# Wordclocktest.net
KiCad netlist of a schematic drawn in EAGLE
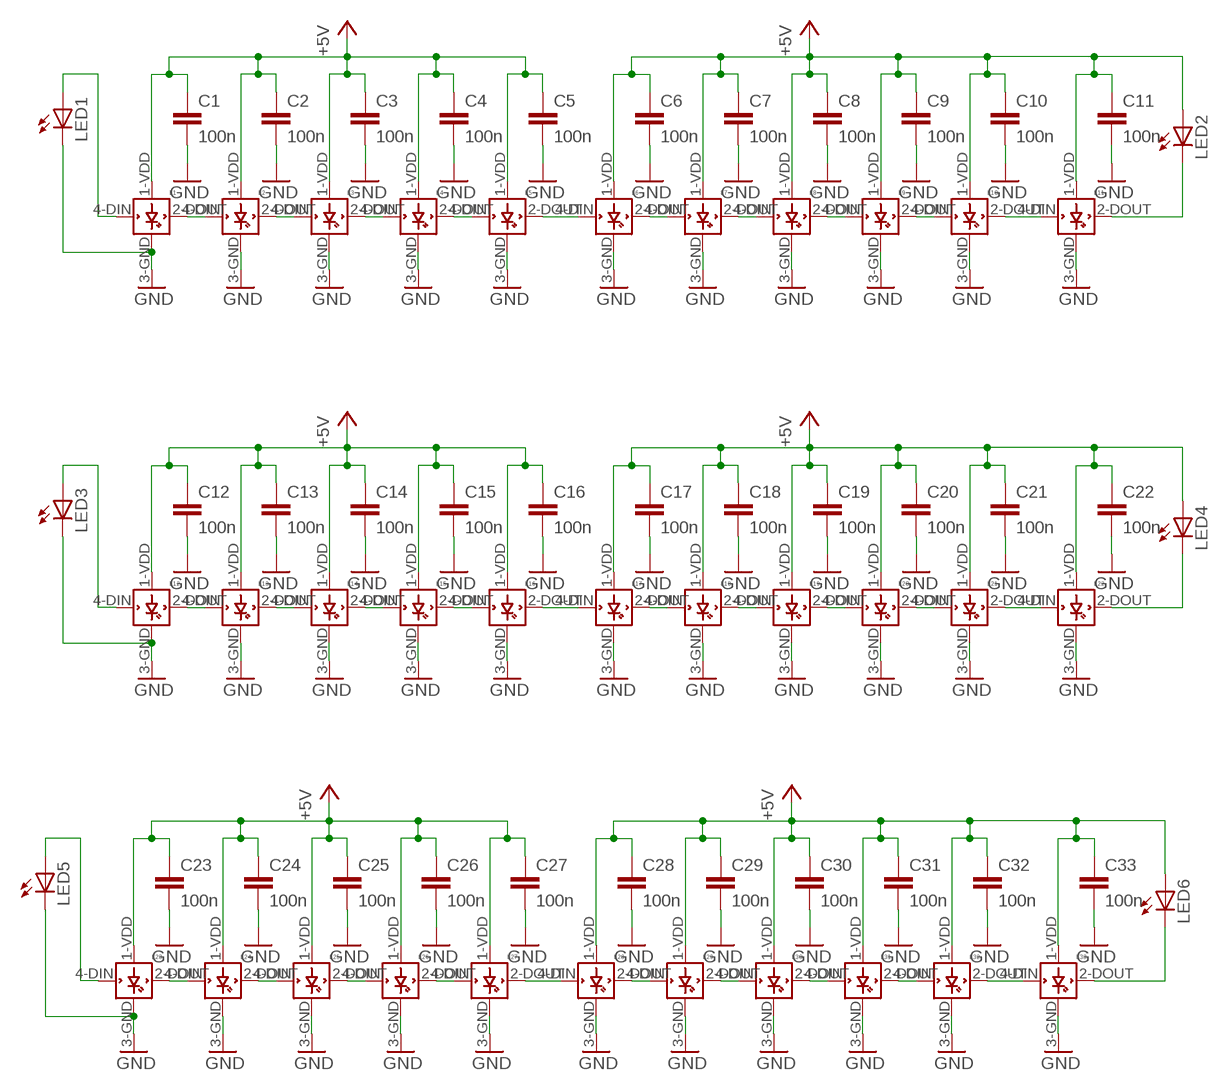
[diagram p0: schematic, sheet 1]

(export (version "E")
  (design (tool "Eeschema 10.0.6"))
  (components
    (comp (ref "C1")
      (value "100n")
      (footprint "eagle-import:C1310")
      (libsource (lib "eagle-import") (part "C-EUC1310"))
    )
    (comp (ref "C2")
      (value "100n")
      (footprint "eagle-import:C1310")
      (libsource (lib "eagle-import") (part "C-EUC1310"))
    )
    (comp (ref "C3")
      (value "100n")
      (footprint "eagle-import:C1310")
      (libsource (lib "eagle-import") (part "C-EUC1310"))
    )
    (comp (ref "C4")
      (value "100n")
      (footprint "eagle-import:C1310")
      (libsource (lib "eagle-import") (part "C-EUC1310"))
    )
    (comp (ref "C5")
      (value "100n")
      (footprint "eagle-import:C1310")
      (libsource (lib "eagle-import") (part "C-EUC1310"))
    )
    (comp (ref "C6")
      (value "100n")
      (footprint "eagle-import:C1310")
      (libsource (lib "eagle-import") (part "C-EUC1310"))
    )
    (comp (ref "C7")
      (value "100n")
      (footprint "eagle-import:C1310")
      (libsource (lib "eagle-import") (part "C-EUC1310"))
    )
    (comp (ref "C8")
      (value "100n")
      (footprint "eagle-import:C1310")
      (libsource (lib "eagle-import") (part "C-EUC1310"))
    )
    (comp (ref "C9")
      (value "100n")
      (footprint "eagle-import:C1310")
      (libsource (lib "eagle-import") (part "C-EUC1310"))
    )
    (comp (ref "C10")
      (value "100n")
      (footprint "eagle-import:C1310")
      (libsource (lib "eagle-import") (part "C-EUC1310"))
    )
    (comp (ref "C11")
      (value "100n")
      (footprint "eagle-import:C1310")
      (libsource (lib "eagle-import") (part "C-EUC1310"))
    )
    (comp (ref "C12")
      (value "100n")
      (footprint "eagle-import:C1310")
      (libsource (lib "eagle-import") (part "C-EUC1310"))
    )
    (comp (ref "C13")
      (value "100n")
      (footprint "eagle-import:C1310")
      (libsource (lib "eagle-import") (part "C-EUC1310"))
    )
    (comp (ref "C14")
      (value "100n")
      (footprint "eagle-import:C1310")
      (libsource (lib "eagle-import") (part "C-EUC1310"))
    )
    (comp (ref "C15")
      (value "100n")
      (footprint "eagle-import:C1310")
      (libsource (lib "eagle-import") (part "C-EUC1310"))
    )
    (comp (ref "C16")
      (value "100n")
      (footprint "eagle-import:C1310")
      (libsource (lib "eagle-import") (part "C-EUC1310"))
    )
    (comp (ref "C17")
      (value "100n")
      (footprint "eagle-import:C1310")
      (libsource (lib "eagle-import") (part "C-EUC1310"))
    )
    (comp (ref "C18")
      (value "100n")
      (footprint "eagle-import:C1310")
      (libsource (lib "eagle-import") (part "C-EUC1310"))
    )
    (comp (ref "C19")
      (value "100n")
      (footprint "eagle-import:C1310")
      (libsource (lib "eagle-import") (part "C-EUC1310"))
    )
    (comp (ref "C20")
      (value "100n")
      (footprint "eagle-import:C1310")
      (libsource (lib "eagle-import") (part "C-EUC1310"))
    )
    (comp (ref "C21")
      (value "100n")
      (footprint "eagle-import:C1310")
      (libsource (lib "eagle-import") (part "C-EUC1310"))
    )
    (comp (ref "C22")
      (value "100n")
      (footprint "eagle-import:C1310")
      (libsource (lib "eagle-import") (part "C-EUC1310"))
    )
    (comp (ref "C23")
      (value "100n")
      (footprint "eagle-import:C1310")
      (libsource (lib "eagle-import") (part "C-EUC1310"))
    )
    (comp (ref "C24")
      (value "100n")
      (footprint "eagle-import:C1310")
      (libsource (lib "eagle-import") (part "C-EUC1310"))
    )
    (comp (ref "C25")
      (value "100n")
      (footprint "eagle-import:C1310")
      (libsource (lib "eagle-import") (part "C-EUC1310"))
    )
    (comp (ref "C26")
      (value "100n")
      (footprint "eagle-import:C1310")
      (libsource (lib "eagle-import") (part "C-EUC1310"))
    )
    (comp (ref "C27")
      (value "100n")
      (footprint "eagle-import:C1310")
      (libsource (lib "eagle-import") (part "C-EUC1310"))
    )
    (comp (ref "C28")
      (value "100n")
      (footprint "eagle-import:C1310")
      (libsource (lib "eagle-import") (part "C-EUC1310"))
    )
    (comp (ref "C29")
      (value "100n")
      (footprint "eagle-import:C1310")
      (libsource (lib "eagle-import") (part "C-EUC1310"))
    )
    (comp (ref "C30")
      (value "100n")
      (footprint "eagle-import:C1310")
      (libsource (lib "eagle-import") (part "C-EUC1310"))
    )
    (comp (ref "C31")
      (value "100n")
      (footprint "eagle-import:C1310")
      (libsource (lib "eagle-import") (part "C-EUC1310"))
    )
    (comp (ref "C32")
      (value "100n")
      (footprint "eagle-import:C1310")
      (libsource (lib "eagle-import") (part "C-EUC1310"))
    )
    (comp (ref "C33")
      (value "100n")
      (footprint "eagle-import:C1310")
      (libsource (lib "eagle-import") (part "C-EUC1310"))
    )
    (comp (ref "L1")
      (value "WS2812B")
      (footprint "eagle-import:WS2812B")
      (libsource (lib "eagle-import") (part "WS2812B"))
    )
    (comp (ref "L2")
      (value "WS2812B")
      (footprint "eagle-import:WS2812B")
      (libsource (lib "eagle-import") (part "WS2812B"))
    )
    (comp (ref "L3")
      (value "WS2812B")
      (footprint "eagle-import:WS2812B")
      (libsource (lib "eagle-import") (part "WS2812B"))
    )
    (comp (ref "L4")
      (value "WS2812B")
      (footprint "eagle-import:WS2812B")
      (libsource (lib "eagle-import") (part "WS2812B"))
    )
    (comp (ref "L5")
      (value "WS2812B")
      (footprint "eagle-import:WS2812B")
      (libsource (lib "eagle-import") (part "WS2812B"))
    )
    (comp (ref "L6")
      (value "WS2812B")
      (footprint "eagle-import:WS2812B")
      (libsource (lib "eagle-import") (part "WS2812B"))
    )
    (comp (ref "L7")
      (value "WS2812B")
      (footprint "eagle-import:WS2812B")
      (libsource (lib "eagle-import") (part "WS2812B"))
    )
    (comp (ref "L8")
      (value "WS2812B")
      (footprint "eagle-import:WS2812B")
      (libsource (lib "eagle-import") (part "WS2812B"))
    )
    (comp (ref "L9")
      (value "WS2812B")
      (footprint "eagle-import:WS2812B")
      (libsource (lib "eagle-import") (part "WS2812B"))
    )
    (comp (ref "L10")
      (value "WS2812B")
      (footprint "eagle-import:WS2812B")
      (libsource (lib "eagle-import") (part "WS2812B"))
    )
    (comp (ref "L11")
      (value "WS2812B")
      (footprint "eagle-import:WS2812B")
      (libsource (lib "eagle-import") (part "WS2812B"))
    )
    (comp (ref "L12")
      (value "WS2812B")
      (footprint "eagle-import:WS2812B")
      (libsource (lib "eagle-import") (part "WS2812B"))
    )
    (comp (ref "L13")
      (value "WS2812B")
      (footprint "eagle-import:WS2812B")
      (libsource (lib "eagle-import") (part "WS2812B"))
    )
    (comp (ref "L14")
      (value "WS2812B")
      (footprint "eagle-import:WS2812B")
      (libsource (lib "eagle-import") (part "WS2812B"))
    )
    (comp (ref "L15")
      (value "WS2812B")
      (footprint "eagle-import:WS2812B")
      (libsource (lib "eagle-import") (part "WS2812B"))
    )
    (comp (ref "L16")
      (value "WS2812B")
      (footprint "eagle-import:WS2812B")
      (libsource (lib "eagle-import") (part "WS2812B"))
    )
    (comp (ref "L17")
      (value "WS2812B")
      (footprint "eagle-import:WS2812B")
      (libsource (lib "eagle-import") (part "WS2812B"))
    )
    (comp (ref "L18")
      (value "WS2812B")
      (footprint "eagle-import:WS2812B")
      (libsource (lib "eagle-import") (part "WS2812B"))
    )
    (comp (ref "L19")
      (value "WS2812B")
      (footprint "eagle-import:WS2812B")
      (libsource (lib "eagle-import") (part "WS2812B"))
    )
    (comp (ref "L20")
      (value "WS2812B")
      (footprint "eagle-import:WS2812B")
      (libsource (lib "eagle-import") (part "WS2812B"))
    )
    (comp (ref "L21")
      (value "WS2812B")
      (footprint "eagle-import:WS2812B")
      (libsource (lib "eagle-import") (part "WS2812B"))
    )
    (comp (ref "L22")
      (value "WS2812B")
      (footprint "eagle-import:WS2812B")
      (libsource (lib "eagle-import") (part "WS2812B"))
    )
    (comp (ref "L23")
      (value "WS2812B")
      (footprint "eagle-import:WS2812B")
      (libsource (lib "eagle-import") (part "WS2812B"))
    )
    (comp (ref "L24")
      (value "WS2812B")
      (footprint "eagle-import:WS2812B")
      (libsource (lib "eagle-import") (part "WS2812B"))
    )
    (comp (ref "L25")
      (value "WS2812B")
      (footprint "eagle-import:WS2812B")
      (libsource (lib "eagle-import") (part "WS2812B"))
    )
    (comp (ref "L26")
      (value "WS2812B")
      (footprint "eagle-import:WS2812B")
      (libsource (lib "eagle-import") (part "WS2812B"))
    )
    (comp (ref "L27")
      (value "WS2812B")
      (footprint "eagle-import:WS2812B")
      (libsource (lib "eagle-import") (part "WS2812B"))
    )
    (comp (ref "L28")
      (value "WS2812B")
      (footprint "eagle-import:WS2812B")
      (libsource (lib "eagle-import") (part "WS2812B"))
    )
    (comp (ref "L29")
      (value "WS2812B")
      (footprint "eagle-import:WS2812B")
      (libsource (lib "eagle-import") (part "WS2812B"))
    )
    (comp (ref "L30")
      (value "WS2812B")
      (footprint "eagle-import:WS2812B")
      (libsource (lib "eagle-import") (part "WS2812B"))
    )
    (comp (ref "L31")
      (value "WS2812B")
      (footprint "eagle-import:WS2812B")
      (libsource (lib "eagle-import") (part "WS2812B"))
    )
    (comp (ref "L32")
      (value "WS2812B")
      (footprint "eagle-import:WS2812B")
      (libsource (lib "eagle-import") (part "WS2812B"))
    )
    (comp (ref "L33")
      (value "WS2812B")
      (footprint "eagle-import:WS2812B")
      (libsource (lib "eagle-import") (part "WS2812B"))
    )
    (comp (ref "LED1")
      (value "LEDCHIP-LED0603")
      (footprint "eagle-import:CHIP-LED0603")
      (libsource (lib "eagle-import") (part "LEDCHIP-LED0603"))
    )
    (comp (ref "LED2")
      (value "LEDCHIP-LED0603")
      (footprint "eagle-import:CHIP-LED0603")
      (libsource (lib "eagle-import") (part "LEDCHIP-LED0603"))
    )
    (comp (ref "LED3")
      (value "LEDCHIP-LED0603")
      (footprint "eagle-import:CHIP-LED0603")
      (libsource (lib "eagle-import") (part "LEDCHIP-LED0603"))
    )
    (comp (ref "LED4")
      (value "LEDCHIP-LED0603")
      (footprint "eagle-import:CHIP-LED0603")
      (libsource (lib "eagle-import") (part "LEDCHIP-LED0603"))
    )
    (comp (ref "LED5")
      (value "LEDCHIP-LED0603")
      (footprint "eagle-import:CHIP-LED0603")
      (libsource (lib "eagle-import") (part "LEDCHIP-LED0603"))
    )
    (comp (ref "LED6")
      (value "LEDCHIP-LED0603")
      (footprint "eagle-import:CHIP-LED0603")
      (libsource (lib "eagle-import") (part "LEDCHIP-LED0603"))
    )
  )
  (nets
    (net (code "1") (name "+5V") (class "Default")
      (node (ref "C1") (pin "1") (pinfunction "1_1") (pintype "passive"))
      (node (ref "C10") (pin "1") (pinfunction "1_1") (pintype "passive"))
      (node (ref "C11") (pin "1") (pinfunction "1_1") (pintype "passive"))
      (node (ref "C12") (pin "1") (pinfunction "1_1") (pintype "passive"))
      (node (ref "C13") (pin "1") (pinfunction "1_1") (pintype "passive"))
      (node (ref "C14") (pin "1") (pinfunction "1_1") (pintype "passive"))
      (node (ref "C15") (pin "1") (pinfunction "1_1") (pintype "passive"))
      (node (ref "C16") (pin "1") (pinfunction "1_1") (pintype "passive"))
      (node (ref "C17") (pin "1") (pinfunction "1_1") (pintype "passive"))
      (node (ref "C18") (pin "1") (pinfunction "1_1") (pintype "passive"))
      (node (ref "C19") (pin "1") (pinfunction "1_1") (pintype "passive"))
      (node (ref "C2") (pin "1") (pinfunction "1_1") (pintype "passive"))
      (node (ref "C20") (pin "1") (pinfunction "1_1") (pintype "passive"))
      (node (ref "C21") (pin "1") (pinfunction "1_1") (pintype "passive"))
      (node (ref "C22") (pin "1") (pinfunction "1_1") (pintype "passive"))
      (node (ref "C23") (pin "1") (pinfunction "1_1") (pintype "passive"))
      (node (ref "C24") (pin "1") (pinfunction "1_1") (pintype "passive"))
      (node (ref "C25") (pin "1") (pinfunction "1_1") (pintype "passive"))
      (node (ref "C26") (pin "1") (pinfunction "1_1") (pintype "passive"))
      (node (ref "C27") (pin "1") (pinfunction "1_1") (pintype "passive"))
      (node (ref "C28") (pin "1") (pinfunction "1_1") (pintype "passive"))
      (node (ref "C29") (pin "1") (pinfunction "1_1") (pintype "passive"))
      (node (ref "C3") (pin "1") (pinfunction "1_1") (pintype "passive"))
      (node (ref "C30") (pin "1") (pinfunction "1_1") (pintype "passive"))
      (node (ref "C31") (pin "1") (pinfunction "1_1") (pintype "passive"))
      (node (ref "C32") (pin "1") (pinfunction "1_1") (pintype "passive"))
      (node (ref "C33") (pin "1") (pinfunction "1_1") (pintype "passive"))
      (node (ref "C4") (pin "1") (pinfunction "1_1") (pintype "passive"))
      (node (ref "C5") (pin "1") (pinfunction "1_1") (pintype "passive"))
      (node (ref "C6") (pin "1") (pinfunction "1_1") (pintype "passive"))
      (node (ref "C7") (pin "1") (pinfunction "1_1") (pintype "passive"))
      (node (ref "C8") (pin "1") (pinfunction "1_1") (pintype "passive"))
      (node (ref "C9") (pin "1") (pinfunction "1_1") (pintype "passive"))
      (node (ref "L1") (pin "1-VDD") (pinfunction "VDD_1-VDD") (pintype "bidirectional"))
      (node (ref "L10") (pin "1-VDD") (pinfunction "VDD_1-VDD") (pintype "bidirectional"))
      (node (ref "L11") (pin "1-VDD") (pinfunction "VDD_1-VDD") (pintype "bidirectional"))
      (node (ref "L12") (pin "1-VDD") (pinfunction "VDD_1-VDD") (pintype "bidirectional"))
      (node (ref "L13") (pin "1-VDD") (pinfunction "VDD_1-VDD") (pintype "bidirectional"))
      (node (ref "L14") (pin "1-VDD") (pinfunction "VDD_1-VDD") (pintype "bidirectional"))
      (node (ref "L15") (pin "1-VDD") (pinfunction "VDD_1-VDD") (pintype "bidirectional"))
      (node (ref "L16") (pin "1-VDD") (pinfunction "VDD_1-VDD") (pintype "bidirectional"))
      (node (ref "L17") (pin "1-VDD") (pinfunction "VDD_1-VDD") (pintype "bidirectional"))
      (node (ref "L18") (pin "1-VDD") (pinfunction "VDD_1-VDD") (pintype "bidirectional"))
      (node (ref "L19") (pin "1-VDD") (pinfunction "VDD_1-VDD") (pintype "bidirectional"))
      (node (ref "L2") (pin "1-VDD") (pinfunction "VDD_1-VDD") (pintype "bidirectional"))
      (node (ref "L20") (pin "1-VDD") (pinfunction "VDD_1-VDD") (pintype "bidirectional"))
      (node (ref "L21") (pin "1-VDD") (pinfunction "VDD_1-VDD") (pintype "bidirectional"))
      (node (ref "L22") (pin "1-VDD") (pinfunction "VDD_1-VDD") (pintype "bidirectional"))
      (node (ref "L23") (pin "1-VDD") (pinfunction "VDD_1-VDD") (pintype "bidirectional"))
      (node (ref "L24") (pin "1-VDD") (pinfunction "VDD_1-VDD") (pintype "bidirectional"))
      (node (ref "L25") (pin "1-VDD") (pinfunction "VDD_1-VDD") (pintype "bidirectional"))
      (node (ref "L26") (pin "1-VDD") (pinfunction "VDD_1-VDD") (pintype "bidirectional"))
      (node (ref "L27") (pin "1-VDD") (pinfunction "VDD_1-VDD") (pintype "bidirectional"))
      (node (ref "L28") (pin "1-VDD") (pinfunction "VDD_1-VDD") (pintype "bidirectional"))
      (node (ref "L29") (pin "1-VDD") (pinfunction "VDD_1-VDD") (pintype "bidirectional"))
      (node (ref "L3") (pin "1-VDD") (pinfunction "VDD_1-VDD") (pintype "bidirectional"))
      (node (ref "L30") (pin "1-VDD") (pinfunction "VDD_1-VDD") (pintype "bidirectional"))
      (node (ref "L31") (pin "1-VDD") (pinfunction "VDD_1-VDD") (pintype "bidirectional"))
      (node (ref "L32") (pin "1-VDD") (pinfunction "VDD_1-VDD") (pintype "bidirectional"))
      (node (ref "L33") (pin "1-VDD") (pinfunction "VDD_1-VDD") (pintype "bidirectional"))
      (node (ref "L4") (pin "1-VDD") (pinfunction "VDD_1-VDD") (pintype "bidirectional"))
      (node (ref "L5") (pin "1-VDD") (pinfunction "VDD_1-VDD") (pintype "bidirectional"))
      (node (ref "L6") (pin "1-VDD") (pinfunction "VDD_1-VDD") (pintype "bidirectional"))
      (node (ref "L7") (pin "1-VDD") (pinfunction "VDD_1-VDD") (pintype "bidirectional"))
      (node (ref "L8") (pin "1-VDD") (pinfunction "VDD_1-VDD") (pintype "bidirectional"))
      (node (ref "L9") (pin "1-VDD") (pinfunction "VDD_1-VDD") (pintype "bidirectional"))
      (node (ref "LED2") (pin "A") (pinfunction "A_A") (pintype "passive"))
      (node (ref "LED4") (pin "A") (pinfunction "A_A") (pintype "passive"))
      (node (ref "LED6") (pin "A") (pinfunction "A_A") (pintype "passive"))
    )
    (net (code "2") (name "GND") (class "Default")
      (node (ref "C1") (pin "2") (pinfunction "2_2") (pintype "passive"))
      (node (ref "C10") (pin "2") (pinfunction "2_2") (pintype "passive"))
      (node (ref "C11") (pin "2") (pinfunction "2_2") (pintype "passive"))
      (node (ref "C12") (pin "2") (pinfunction "2_2") (pintype "passive"))
      (node (ref "C13") (pin "2") (pinfunction "2_2") (pintype "passive"))
      (node (ref "C14") (pin "2") (pinfunction "2_2") (pintype "passive"))
      (node (ref "C15") (pin "2") (pinfunction "2_2") (pintype "passive"))
      (node (ref "C16") (pin "2") (pinfunction "2_2") (pintype "passive"))
      (node (ref "C17") (pin "2") (pinfunction "2_2") (pintype "passive"))
      (node (ref "C18") (pin "2") (pinfunction "2_2") (pintype "passive"))
      (node (ref "C19") (pin "2") (pinfunction "2_2") (pintype "passive"))
      (node (ref "C2") (pin "2") (pinfunction "2_2") (pintype "passive"))
      (node (ref "C20") (pin "2") (pinfunction "2_2") (pintype "passive"))
      (node (ref "C21") (pin "2") (pinfunction "2_2") (pintype "passive"))
      (node (ref "C22") (pin "2") (pinfunction "2_2") (pintype "passive"))
      (node (ref "C23") (pin "2") (pinfunction "2_2") (pintype "passive"))
      (node (ref "C24") (pin "2") (pinfunction "2_2") (pintype "passive"))
      (node (ref "C25") (pin "2") (pinfunction "2_2") (pintype "passive"))
      (node (ref "C26") (pin "2") (pinfunction "2_2") (pintype "passive"))
      (node (ref "C27") (pin "2") (pinfunction "2_2") (pintype "passive"))
      (node (ref "C28") (pin "2") (pinfunction "2_2") (pintype "passive"))
      (node (ref "C29") (pin "2") (pinfunction "2_2") (pintype "passive"))
      (node (ref "C3") (pin "2") (pinfunction "2_2") (pintype "passive"))
      (node (ref "C30") (pin "2") (pinfunction "2_2") (pintype "passive"))
      (node (ref "C31") (pin "2") (pinfunction "2_2") (pintype "passive"))
      (node (ref "C32") (pin "2") (pinfunction "2_2") (pintype "passive"))
      (node (ref "C33") (pin "2") (pinfunction "2_2") (pintype "passive"))
      (node (ref "C4") (pin "2") (pinfunction "2_2") (pintype "passive"))
      (node (ref "C5") (pin "2") (pinfunction "2_2") (pintype "passive"))
      (node (ref "C6") (pin "2") (pinfunction "2_2") (pintype "passive"))
      (node (ref "C7") (pin "2") (pinfunction "2_2") (pintype "passive"))
      (node (ref "C8") (pin "2") (pinfunction "2_2") (pintype "passive"))
      (node (ref "C9") (pin "2") (pinfunction "2_2") (pintype "passive"))
      (node (ref "L1") (pin "3-GND") (pinfunction "GND_3-GND") (pintype "bidirectional"))
      (node (ref "L10") (pin "3-GND") (pinfunction "GND_3-GND") (pintype "bidirectional"))
      (node (ref "L11") (pin "3-GND") (pinfunction "GND_3-GND") (pintype "bidirectional"))
      (node (ref "L12") (pin "3-GND") (pinfunction "GND_3-GND") (pintype "bidirectional"))
      (node (ref "L13") (pin "3-GND") (pinfunction "GND_3-GND") (pintype "bidirectional"))
      (node (ref "L14") (pin "3-GND") (pinfunction "GND_3-GND") (pintype "bidirectional"))
      (node (ref "L15") (pin "3-GND") (pinfunction "GND_3-GND") (pintype "bidirectional"))
      (node (ref "L16") (pin "3-GND") (pinfunction "GND_3-GND") (pintype "bidirectional"))
      (node (ref "L17") (pin "3-GND") (pinfunction "GND_3-GND") (pintype "bidirectional"))
      (node (ref "L18") (pin "3-GND") (pinfunction "GND_3-GND") (pintype "bidirectional"))
      (node (ref "L19") (pin "3-GND") (pinfunction "GND_3-GND") (pintype "bidirectional"))
      (node (ref "L2") (pin "3-GND") (pinfunction "GND_3-GND") (pintype "bidirectional"))
      (node (ref "L20") (pin "3-GND") (pinfunction "GND_3-GND") (pintype "bidirectional"))
      (node (ref "L21") (pin "3-GND") (pinfunction "GND_3-GND") (pintype "bidirectional"))
      (node (ref "L22") (pin "3-GND") (pinfunction "GND_3-GND") (pintype "bidirectional"))
      (node (ref "L23") (pin "3-GND") (pinfunction "GND_3-GND") (pintype "bidirectional"))
      (node (ref "L24") (pin "3-GND") (pinfunction "GND_3-GND") (pintype "bidirectional"))
      (node (ref "L25") (pin "3-GND") (pinfunction "GND_3-GND") (pintype "bidirectional"))
      (node (ref "L26") (pin "3-GND") (pinfunction "GND_3-GND") (pintype "bidirectional"))
      (node (ref "L27") (pin "3-GND") (pinfunction "GND_3-GND") (pintype "bidirectional"))
      (node (ref "L28") (pin "3-GND") (pinfunction "GND_3-GND") (pintype "bidirectional"))
      (node (ref "L29") (pin "3-GND") (pinfunction "GND_3-GND") (pintype "bidirectional"))
      (node (ref "L3") (pin "3-GND") (pinfunction "GND_3-GND") (pintype "bidirectional"))
      (node (ref "L30") (pin "3-GND") (pinfunction "GND_3-GND") (pintype "bidirectional"))
      (node (ref "L31") (pin "3-GND") (pinfunction "GND_3-GND") (pintype "bidirectional"))
      (node (ref "L32") (pin "3-GND") (pinfunction "GND_3-GND") (pintype "bidirectional"))
      (node (ref "L33") (pin "3-GND") (pinfunction "GND_3-GND") (pintype "bidirectional"))
      (node (ref "L4") (pin "3-GND") (pinfunction "GND_3-GND") (pintype "bidirectional"))
      (node (ref "L5") (pin "3-GND") (pinfunction "GND_3-GND") (pintype "bidirectional"))
      (node (ref "L6") (pin "3-GND") (pinfunction "GND_3-GND") (pintype "bidirectional"))
      (node (ref "L7") (pin "3-GND") (pinfunction "GND_3-GND") (pintype "bidirectional"))
      (node (ref "L8") (pin "3-GND") (pinfunction "GND_3-GND") (pintype "bidirectional"))
      (node (ref "L9") (pin "3-GND") (pinfunction "GND_3-GND") (pintype "bidirectional"))
      (node (ref "LED1") (pin "C") (pinfunction "C_C") (pintype "passive"))
      (node (ref "LED3") (pin "C") (pinfunction "C_C") (pintype "passive"))
      (node (ref "LED5") (pin "C") (pinfunction "C_C") (pintype "passive"))
    )
    (net (code "3") (name "Net-(L1-DIN)") (class "Default")
      (node (ref "L1") (pin "4-DIN") (pinfunction "DIN_4-DIN") (pintype "input"))
      (node (ref "LED1") (pin "A") (pinfunction "A_A") (pintype "passive"))
    )
    (net (code "4") (name "Net-(L1-DOUT)") (class "Default")
      (node (ref "L1") (pin "2-DOUT") (pinfunction "DOUT_2-DOUT") (pintype "output"))
      (node (ref "L2") (pin "4-DIN") (pinfunction "DIN_4-DIN") (pintype "input"))
    )
    (net (code "5") (name "Net-(L2-DOUT)") (class "Default")
      (node (ref "L2") (pin "2-DOUT") (pinfunction "DOUT_2-DOUT") (pintype "output"))
      (node (ref "L3") (pin "4-DIN") (pinfunction "DIN_4-DIN") (pintype "input"))
    )
    (net (code "6") (name "Net-(L3-DOUT)") (class "Default")
      (node (ref "L3") (pin "2-DOUT") (pinfunction "DOUT_2-DOUT") (pintype "output"))
      (node (ref "L4") (pin "4-DIN") (pinfunction "DIN_4-DIN") (pintype "input"))
    )
    (net (code "7") (name "Net-(L4-DOUT)") (class "Default")
      (node (ref "L4") (pin "2-DOUT") (pinfunction "DOUT_2-DOUT") (pintype "output"))
      (node (ref "L5") (pin "4-DIN") (pinfunction "DIN_4-DIN") (pintype "input"))
    )
    (net (code "8") (name "Net-(L5-DOUT)") (class "Default")
      (node (ref "L5") (pin "2-DOUT") (pinfunction "DOUT_2-DOUT") (pintype "output"))
      (node (ref "L6") (pin "4-DIN") (pinfunction "DIN_4-DIN") (pintype "input"))
    )
    (net (code "9") (name "Net-(L6-DOUT)") (class "Default")
      (node (ref "L6") (pin "2-DOUT") (pinfunction "DOUT_2-DOUT") (pintype "output"))
      (node (ref "L7") (pin "4-DIN") (pinfunction "DIN_4-DIN") (pintype "input"))
    )
    (net (code "10") (name "Net-(L7-DOUT)") (class "Default")
      (node (ref "L7") (pin "2-DOUT") (pinfunction "DOUT_2-DOUT") (pintype "output"))
      (node (ref "L8") (pin "4-DIN") (pinfunction "DIN_4-DIN") (pintype "input"))
    )
    (net (code "11") (name "Net-(L8-DOUT)") (class "Default")
      (node (ref "L8") (pin "2-DOUT") (pinfunction "DOUT_2-DOUT") (pintype "output"))
      (node (ref "L9") (pin "4-DIN") (pinfunction "DIN_4-DIN") (pintype "input"))
    )
    (net (code "12") (name "Net-(L10-DIN)") (class "Default")
      (node (ref "L10") (pin "4-DIN") (pinfunction "DIN_4-DIN") (pintype "input"))
      (node (ref "L9") (pin "2-DOUT") (pinfunction "DOUT_2-DOUT") (pintype "output"))
    )
    (net (code "13") (name "Net-(L10-DOUT)") (class "Default")
      (node (ref "L10") (pin "2-DOUT") (pinfunction "DOUT_2-DOUT") (pintype "output"))
      (node (ref "L11") (pin "4-DIN") (pinfunction "DIN_4-DIN") (pintype "input"))
    )
    (net (code "14") (name "Net-(L11-DOUT)") (class "Default")
      (node (ref "L11") (pin "2-DOUT") (pinfunction "DOUT_2-DOUT") (pintype "output"))
      (node (ref "LED2") (pin "C") (pinfunction "C_C") (pintype "passive"))
    )
    (net (code "15") (name "Net-(L12-DIN)") (class "Default")
      (node (ref "L12") (pin "4-DIN") (pinfunction "DIN_4-DIN") (pintype "input"))
      (node (ref "LED3") (pin "A") (pinfunction "A_A") (pintype "passive"))
    )
    (net (code "16") (name "Net-(L12-DOUT)") (class "Default")
      (node (ref "L12") (pin "2-DOUT") (pinfunction "DOUT_2-DOUT") (pintype "output"))
      (node (ref "L13") (pin "4-DIN") (pinfunction "DIN_4-DIN") (pintype "input"))
    )
    (net (code "17") (name "Net-(L13-DOUT)") (class "Default")
      (node (ref "L13") (pin "2-DOUT") (pinfunction "DOUT_2-DOUT") (pintype "output"))
      (node (ref "L14") (pin "4-DIN") (pinfunction "DIN_4-DIN") (pintype "input"))
    )
    (net (code "18") (name "Net-(L14-DOUT)") (class "Default")
      (node (ref "L14") (pin "2-DOUT") (pinfunction "DOUT_2-DOUT") (pintype "output"))
      (node (ref "L15") (pin "4-DIN") (pinfunction "DIN_4-DIN") (pintype "input"))
    )
    (net (code "19") (name "Net-(L15-DOUT)") (class "Default")
      (node (ref "L15") (pin "2-DOUT") (pinfunction "DOUT_2-DOUT") (pintype "output"))
      (node (ref "L16") (pin "4-DIN") (pinfunction "DIN_4-DIN") (pintype "input"))
    )
    (net (code "20") (name "Net-(L16-DOUT)") (class "Default")
      (node (ref "L16") (pin "2-DOUT") (pinfunction "DOUT_2-DOUT") (pintype "output"))
      (node (ref "L17") (pin "4-DIN") (pinfunction "DIN_4-DIN") (pintype "input"))
    )
    (net (code "21") (name "Net-(L17-DOUT)") (class "Default")
      (node (ref "L17") (pin "2-DOUT") (pinfunction "DOUT_2-DOUT") (pintype "output"))
      (node (ref "L18") (pin "4-DIN") (pinfunction "DIN_4-DIN") (pintype "input"))
    )
    (net (code "22") (name "Net-(L18-DOUT)") (class "Default")
      (node (ref "L18") (pin "2-DOUT") (pinfunction "DOUT_2-DOUT") (pintype "output"))
      (node (ref "L19") (pin "4-DIN") (pinfunction "DIN_4-DIN") (pintype "input"))
    )
    (net (code "23") (name "Net-(L19-DOUT)") (class "Default")
      (node (ref "L19") (pin "2-DOUT") (pinfunction "DOUT_2-DOUT") (pintype "output"))
      (node (ref "L20") (pin "4-DIN") (pinfunction "DIN_4-DIN") (pintype "input"))
    )
    (net (code "24") (name "Net-(L20-DOUT)") (class "Default")
      (node (ref "L20") (pin "2-DOUT") (pinfunction "DOUT_2-DOUT") (pintype "output"))
      (node (ref "L21") (pin "4-DIN") (pinfunction "DIN_4-DIN") (pintype "input"))
    )
    (net (code "25") (name "Net-(L21-DOUT)") (class "Default")
      (node (ref "L21") (pin "2-DOUT") (pinfunction "DOUT_2-DOUT") (pintype "output"))
      (node (ref "L22") (pin "4-DIN") (pinfunction "DIN_4-DIN") (pintype "input"))
    )
    (net (code "26") (name "Net-(L22-DOUT)") (class "Default")
      (node (ref "L22") (pin "2-DOUT") (pinfunction "DOUT_2-DOUT") (pintype "output"))
      (node (ref "LED4") (pin "C") (pinfunction "C_C") (pintype "passive"))
    )
    (net (code "27") (name "Net-(L23-DIN)") (class "Default")
      (node (ref "L23") (pin "4-DIN") (pinfunction "DIN_4-DIN") (pintype "input"))
      (node (ref "LED5") (pin "A") (pinfunction "A_A") (pintype "passive"))
    )
    (net (code "28") (name "Net-(L23-DOUT)") (class "Default")
      (node (ref "L23") (pin "2-DOUT") (pinfunction "DOUT_2-DOUT") (pintype "output"))
      (node (ref "L24") (pin "4-DIN") (pinfunction "DIN_4-DIN") (pintype "input"))
    )
    (net (code "29") (name "Net-(L24-DOUT)") (class "Default")
      (node (ref "L24") (pin "2-DOUT") (pinfunction "DOUT_2-DOUT") (pintype "output"))
      (node (ref "L25") (pin "4-DIN") (pinfunction "DIN_4-DIN") (pintype "input"))
    )
    (net (code "30") (name "Net-(L25-DOUT)") (class "Default")
      (node (ref "L25") (pin "2-DOUT") (pinfunction "DOUT_2-DOUT") (pintype "output"))
      (node (ref "L26") (pin "4-DIN") (pinfunction "DIN_4-DIN") (pintype "input"))
    )
    (net (code "31") (name "Net-(L26-DOUT)") (class "Default")
      (node (ref "L26") (pin "2-DOUT") (pinfunction "DOUT_2-DOUT") (pintype "output"))
      (node (ref "L27") (pin "4-DIN") (pinfunction "DIN_4-DIN") (pintype "input"))
    )
    (net (code "32") (name "Net-(L27-DOUT)") (class "Default")
      (node (ref "L27") (pin "2-DOUT") (pinfunction "DOUT_2-DOUT") (pintype "output"))
      (node (ref "L28") (pin "4-DIN") (pinfunction "DIN_4-DIN") (pintype "input"))
    )
    (net (code "33") (name "Net-(L28-DOUT)") (class "Default")
      (node (ref "L28") (pin "2-DOUT") (pinfunction "DOUT_2-DOUT") (pintype "output"))
      (node (ref "L29") (pin "4-DIN") (pinfunction "DIN_4-DIN") (pintype "input"))
    )
    (net (code "34") (name "Net-(L29-DOUT)") (class "Default")
      (node (ref "L29") (pin "2-DOUT") (pinfunction "DOUT_2-DOUT") (pintype "output"))
      (node (ref "L30") (pin "4-DIN") (pinfunction "DIN_4-DIN") (pintype "input"))
    )
    (net (code "35") (name "Net-(L30-DOUT)") (class "Default")
      (node (ref "L30") (pin "2-DOUT") (pinfunction "DOUT_2-DOUT") (pintype "output"))
      (node (ref "L31") (pin "4-DIN") (pinfunction "DIN_4-DIN") (pintype "input"))
    )
    (net (code "36") (name "Net-(L31-DOUT)") (class "Default")
      (node (ref "L31") (pin "2-DOUT") (pinfunction "DOUT_2-DOUT") (pintype "output"))
      (node (ref "L32") (pin "4-DIN") (pinfunction "DIN_4-DIN") (pintype "input"))
    )
    (net (code "37") (name "Net-(L32-DOUT)") (class "Default")
      (node (ref "L32") (pin "2-DOUT") (pinfunction "DOUT_2-DOUT") (pintype "output"))
      (node (ref "L33") (pin "4-DIN") (pinfunction "DIN_4-DIN") (pintype "input"))
    )
    (net (code "38") (name "Net-(L33-DOUT)") (class "Default")
      (node (ref "L33") (pin "2-DOUT") (pinfunction "DOUT_2-DOUT") (pintype "output"))
      (node (ref "LED6") (pin "C") (pinfunction "C_C") (pintype "passive"))
    )
  )
)
